# Signal_Multiplexers.net
KiCad netlist of a schematic drawn in Altium Designer
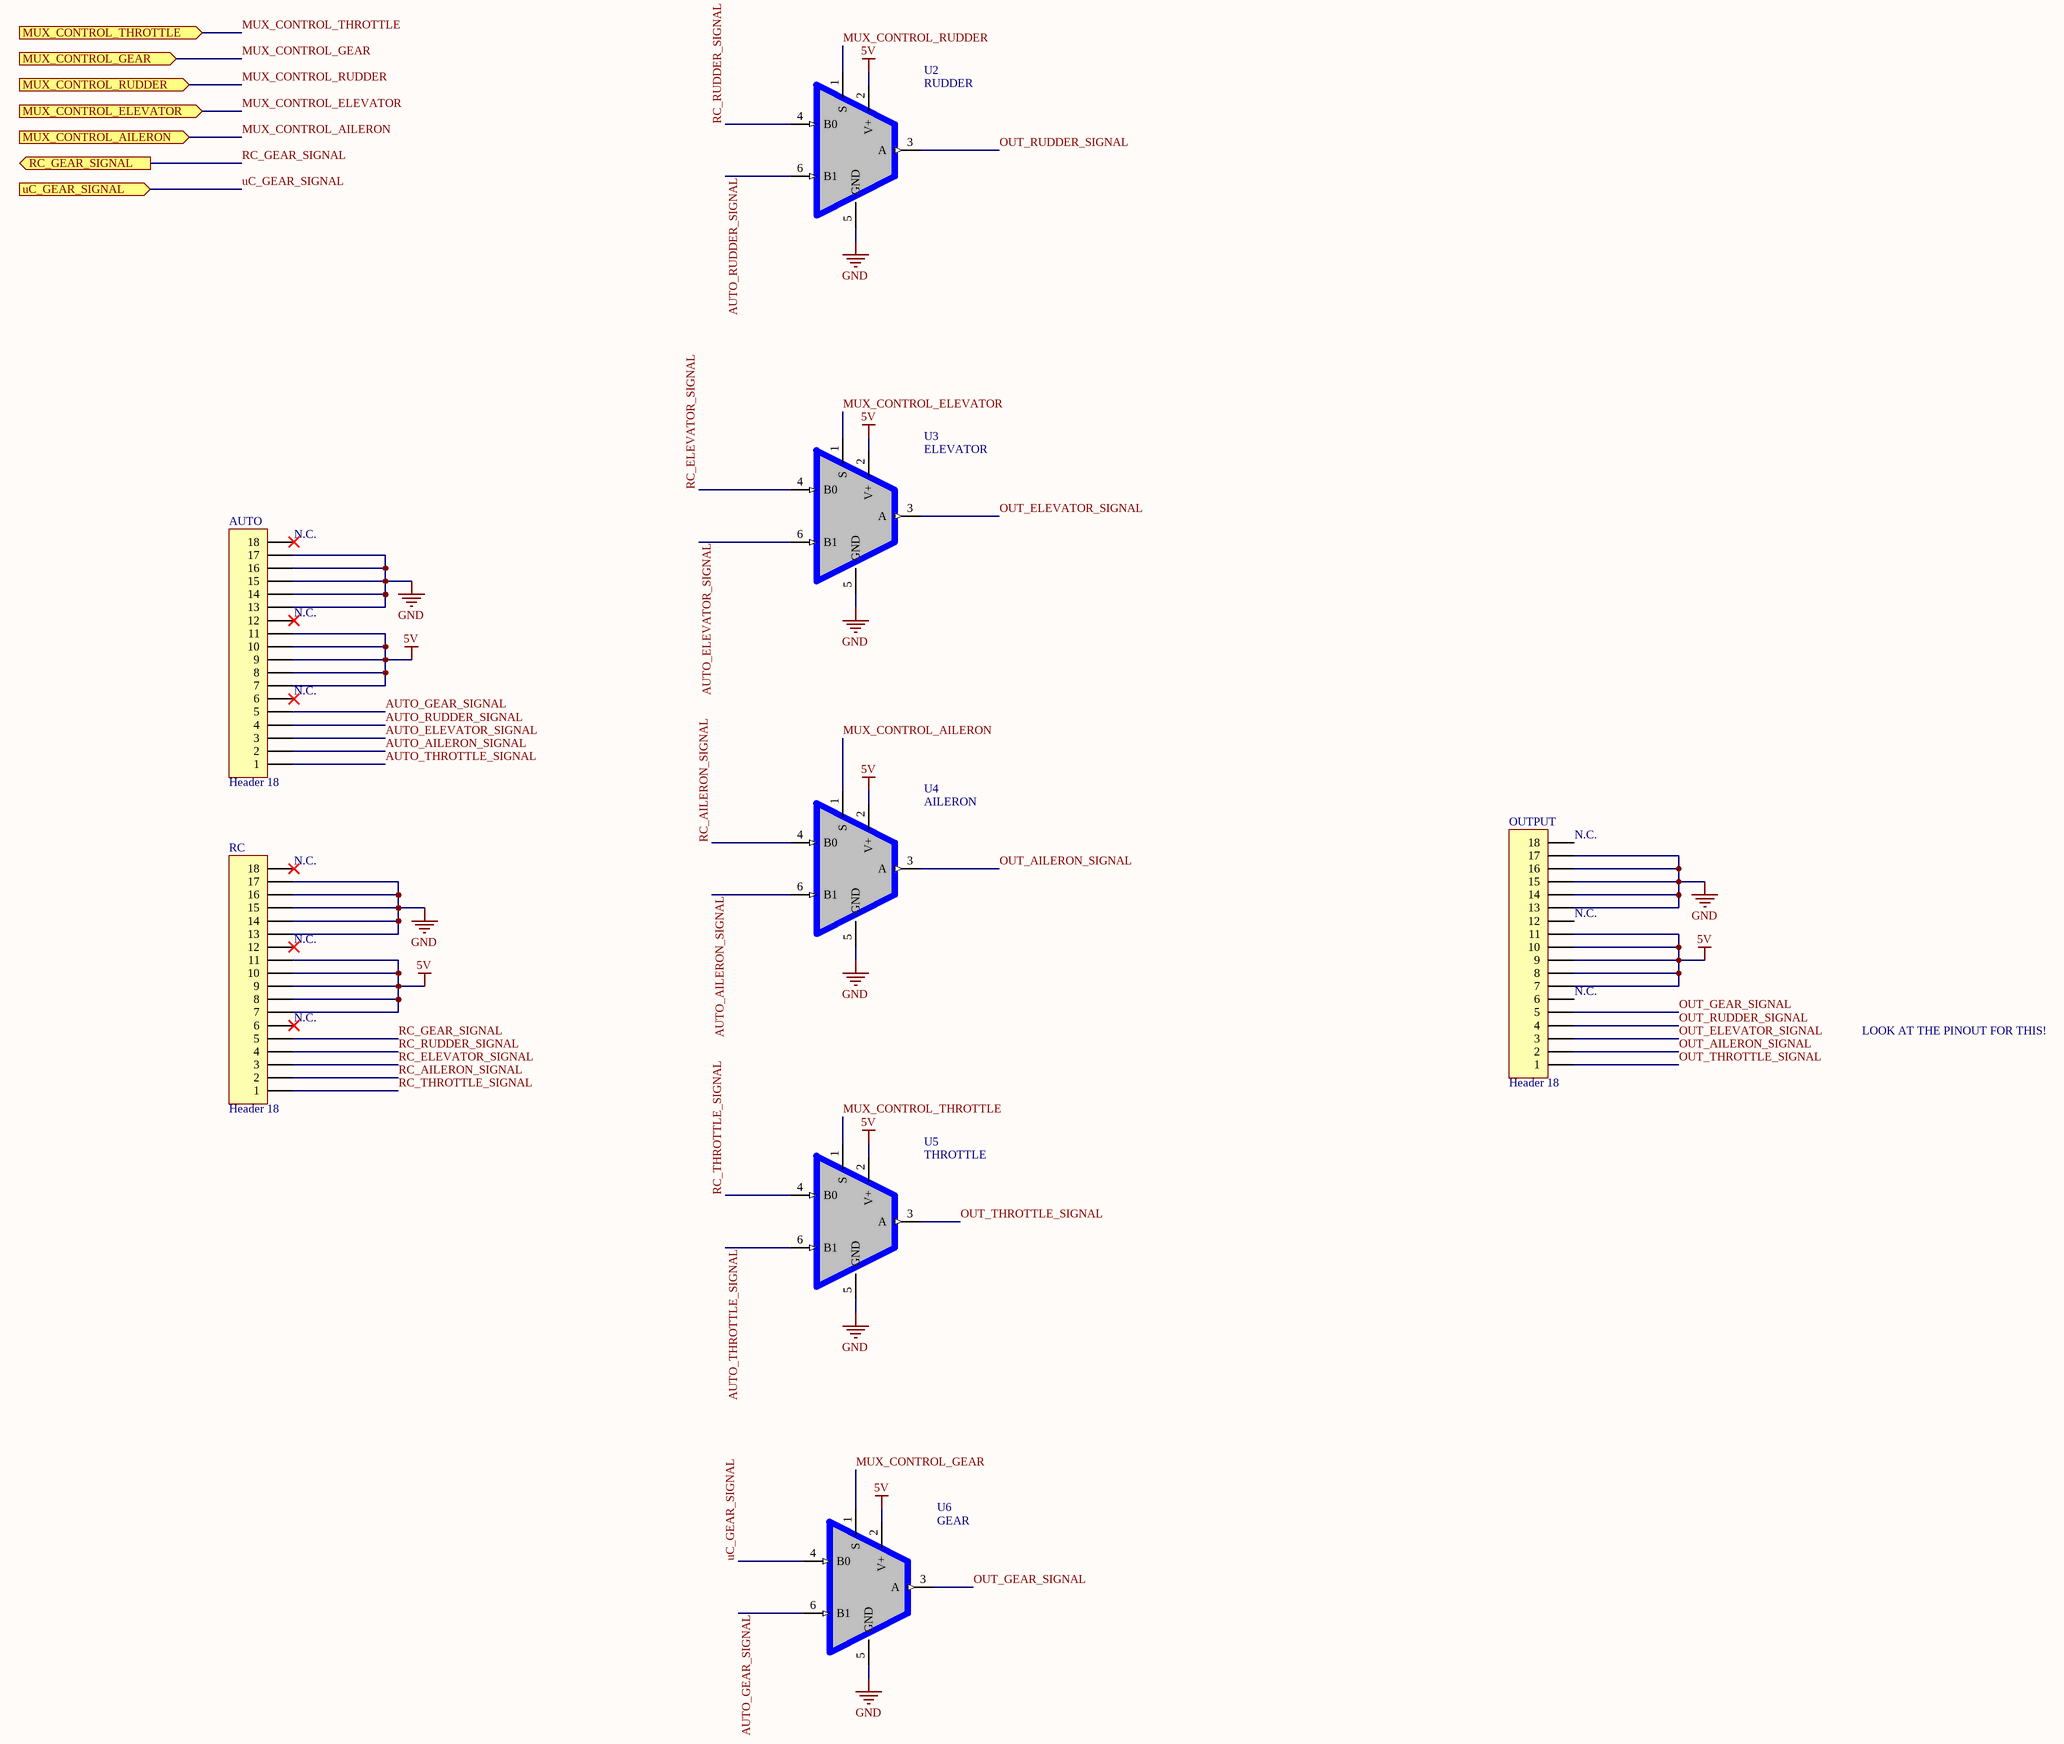
[diagram p0: Signal_Multiplexers.SchDoc]

(export (version "E")
  (design (tool "Eeschema 10.0.6"))
  (components
    (comp (ref "AUTO")
      (value "Header 18")
      (footprint "PCBComponent_1")
      (description "Header, 18-Pin")
      (fields
        (field (name "MANUFACTURER") "Preci-Dip")
        (field (name "MANUFACTURER PART NUMBER") "894-80-030-20-001101")
        (field (name "PUBLISHER") "Altium Limited")
      )
      (libsource (lib "Miscellaneous Connectors") (part "Header 18"))
    )
    (comp (ref "OUTPUT")
      (value "Header 18")
      (footprint "PCBComponent_1")
      (description "Header, 18-Pin")
      (fields
        (field (name "MANUFACTURER") "Preci-Dip")
        (field (name "MANUFACTURER PART NUMBER") "894-80-030-20-001101")
        (field (name "PUBLISHER") "Altium Limited")
      )
      (libsource (lib "Miscellaneous Connectors") (part "Header 18"))
    )
    (comp (ref "RC")
      (value "Header 18")
      (footprint "PCBComponent_1")
      (description "Header, 18-Pin")
      (fields
        (field (name "MANUFACTURER") "Preci-Dip")
        (field (name "MANUFACTURER PART NUMBER") "894-80-030-20-001101")
        (field (name "PUBLISHER") "Altium Limited")
      )
      (libsource (lib "Miscellaneous Connectors") (part "Header 18"))
    )
    (comp (ref "U2")
      (value "RUDDER")
      (footprint "uDFN-6L")
      (description "Multiplexer Switch ICs SPDT 2:1 Mutiplxr 1.65-5.5V; 0.7ohm")
      (libsource (lib "Vishay_Digital_Multiplexers") (part "DG4157EDN"))
    )
    (comp (ref "U3")
      (value "ELEVATOR")
      (footprint "uDFN-6L")
      (description "Multiplexer Switch ICs SPDT 2:1 Mutiplxr 1.65-5.5V; 0.7ohm")
      (libsource (lib "Vishay_Digital_Multiplexers") (part "DG4157EDN"))
    )
    (comp (ref "U4")
      (value "AILERON")
      (footprint "uDFN-6L")
      (description "Multiplexer Switch ICs SPDT 2:1 Mutiplxr 1.65-5.5V; 0.7ohm")
      (libsource (lib "Vishay_Digital_Multiplexers") (part "DG4157EDN"))
    )
    (comp (ref "U5")
      (value "THROTTLE")
      (footprint "uDFN-6L")
      (description "Multiplexer Switch ICs SPDT 2:1 Mutiplxr 1.65-5.5V; 0.7ohm")
      (libsource (lib "Vishay_Digital_Multiplexers") (part "DG4157EDN"))
    )
    (comp (ref "U6")
      (value "GEAR")
      (footprint "uDFN-6L")
      (description "Multiplexer Switch ICs SPDT 2:1 Mutiplxr 1.65-5.5V; 0.7ohm")
      (libsource (lib "Vishay_Digital_Multiplexers") (part "DG4157EDN"))
    )
  )
  (nets
    (net (code "1") (name "/AUTO_AILERON_SIGNAL") (class "Default")
      (node (ref "AUTO") (pin "2") (pinfunction "2_2") (pintype "passive"))
      (node (ref "U4") (pin "6") (pinfunction "B1_6") (pintype "input"))
    )
    (net (code "2") (name "/AUTO_ELEVATOR_SIGNAL") (class "Default")
      (node (ref "AUTO") (pin "3") (pinfunction "3_3") (pintype "passive"))
      (node (ref "U3") (pin "6") (pinfunction "B1_6") (pintype "input"))
    )
    (net (code "3") (name "/AUTO_GEAR_SIGNAL") (class "Default")
      (node (ref "AUTO") (pin "5") (pinfunction "5_5") (pintype "passive"))
      (node (ref "U6") (pin "6") (pinfunction "B1_6") (pintype "input"))
    )
    (net (code "4") (name "/AUTO_RUDDER_SIGNAL") (class "Default")
      (node (ref "AUTO") (pin "4") (pinfunction "4_4") (pintype "passive"))
      (node (ref "U2") (pin "6") (pinfunction "B1_6") (pintype "input"))
    )
    (net (code "5") (name "/AUTO_THROTTLE_SIGNAL") (class "Default")
      (node (ref "AUTO") (pin "1") (pinfunction "1_1") (pintype "passive"))
      (node (ref "U5") (pin "6") (pinfunction "B1_6") (pintype "input"))
    )
    (net (code "6") (name "/MUX_CONTROL_AILERON") (class "Default")
      (node (ref "U4") (pin "1") (pinfunction "S_1") (pintype "passive"))
    )
    (net (code "7") (name "/MUX_CONTROL_ELEVATOR") (class "Default")
      (node (ref "U3") (pin "1") (pinfunction "S_1") (pintype "passive"))
    )
    (net (code "8") (name "/MUX_CONTROL_GEAR") (class "Default")
      (node (ref "U6") (pin "1") (pinfunction "S_1") (pintype "passive"))
    )
    (net (code "9") (name "/MUX_CONTROL_RUDDER") (class "Default")
      (node (ref "U2") (pin "1") (pinfunction "S_1") (pintype "passive"))
    )
    (net (code "10") (name "/MUX_CONTROL_THROTTLE") (class "Default")
      (node (ref "U5") (pin "1") (pinfunction "S_1") (pintype "passive"))
    )
    (net (code "11") (name "/OUT_AILERON_SIGNAL") (class "Default")
      (node (ref "OUTPUT") (pin "2") (pinfunction "2_2") (pintype "passive"))
      (node (ref "U4") (pin "3") (pinfunction "A_3") (pintype "output"))
    )
    (net (code "12") (name "/OUT_ELEVATOR_SIGNAL") (class "Default")
      (node (ref "OUTPUT") (pin "3") (pinfunction "3_3") (pintype "passive"))
      (node (ref "U3") (pin "3") (pinfunction "A_3") (pintype "output"))
    )
    (net (code "13") (name "/OUT_GEAR_SIGNAL") (class "Default")
      (node (ref "OUTPUT") (pin "5") (pinfunction "5_5") (pintype "passive"))
      (node (ref "U6") (pin "3") (pinfunction "A_3") (pintype "output"))
    )
    (net (code "14") (name "/OUT_RUDDER_SIGNAL") (class "Default")
      (node (ref "OUTPUT") (pin "4") (pinfunction "4_4") (pintype "passive"))
      (node (ref "U2") (pin "3") (pinfunction "A_3") (pintype "output"))
    )
    (net (code "15") (name "/OUT_THROTTLE_SIGNAL") (class "Default")
      (node (ref "OUTPUT") (pin "1") (pinfunction "1_1") (pintype "passive"))
      (node (ref "U5") (pin "3") (pinfunction "A_3") (pintype "output"))
    )
    (net (code "16") (name "/RC_AILERON_SIGNAL") (class "Default")
      (node (ref "RC") (pin "2") (pinfunction "2_2") (pintype "passive"))
      (node (ref "U4") (pin "4") (pinfunction "B0_4") (pintype "input"))
    )
    (net (code "17") (name "/RC_ELEVATOR_SIGNAL") (class "Default")
      (node (ref "RC") (pin "3") (pinfunction "3_3") (pintype "passive"))
      (node (ref "U3") (pin "4") (pinfunction "B0_4") (pintype "input"))
    )
    (net (code "18") (name "/RC_GEAR_SIGNAL") (class "Default")
      (node (ref "RC") (pin "5") (pinfunction "5_5") (pintype "passive"))
    )
    (net (code "19") (name "/RC_RUDDER_SIGNAL") (class "Default")
      (node (ref "RC") (pin "4") (pinfunction "4_4") (pintype "passive"))
      (node (ref "U2") (pin "4") (pinfunction "B0_4") (pintype "input"))
    )
    (net (code "20") (name "/RC_THROTTLE_SIGNAL") (class "Default")
      (node (ref "RC") (pin "1") (pinfunction "1_1") (pintype "passive"))
      (node (ref "U5") (pin "4") (pinfunction "B0_4") (pintype "input"))
    )
    (net (code "21") (name "/uC_GEAR_SIGNAL") (class "Default")
      (node (ref "U6") (pin "4") (pinfunction "B0_4") (pintype "input"))
    )
    (net (code "22") (name "5V") (class "Default")
      (node (ref "AUTO") (pin "10") (pinfunction "10_10") (pintype "passive"))
      (node (ref "AUTO") (pin "11") (pinfunction "11_11") (pintype "passive"))
      (node (ref "AUTO") (pin "7") (pinfunction "7_7") (pintype "passive"))
      (node (ref "AUTO") (pin "8") (pinfunction "8_8") (pintype "passive"))
      (node (ref "AUTO") (pin "9") (pinfunction "9_9") (pintype "passive"))
      (node (ref "OUTPUT") (pin "10") (pinfunction "10_10") (pintype "passive"))
      (node (ref "OUTPUT") (pin "11") (pinfunction "11_11") (pintype "passive"))
      (node (ref "OUTPUT") (pin "7") (pinfunction "7_7") (pintype "passive"))
      (node (ref "OUTPUT") (pin "8") (pinfunction "8_8") (pintype "passive"))
      (node (ref "OUTPUT") (pin "9") (pinfunction "9_9") (pintype "passive"))
      (node (ref "RC") (pin "10") (pinfunction "10_10") (pintype "passive"))
      (node (ref "RC") (pin "11") (pinfunction "11_11") (pintype "passive"))
      (node (ref "RC") (pin "7") (pinfunction "7_7") (pintype "passive"))
      (node (ref "RC") (pin "8") (pinfunction "8_8") (pintype "passive"))
      (node (ref "RC") (pin "9") (pinfunction "9_9") (pintype "passive"))
      (node (ref "U2") (pin "2") (pinfunction "V+_2") (pintype "power_in"))
      (node (ref "U3") (pin "2") (pinfunction "V+_2") (pintype "power_in"))
      (node (ref "U4") (pin "2") (pinfunction "V+_2") (pintype "power_in"))
      (node (ref "U5") (pin "2") (pinfunction "V+_2") (pintype "power_in"))
      (node (ref "U6") (pin "2") (pinfunction "V+_2") (pintype "power_in"))
    )
    (net (code "23") (name "GND") (class "Default")
      (node (ref "AUTO") (pin "13") (pinfunction "13_13") (pintype "passive"))
      (node (ref "AUTO") (pin "14") (pinfunction "14_14") (pintype "passive"))
      (node (ref "AUTO") (pin "15") (pinfunction "15_15") (pintype "passive"))
      (node (ref "AUTO") (pin "16") (pinfunction "16_16") (pintype "passive"))
      (node (ref "AUTO") (pin "17") (pinfunction "17_17") (pintype "passive"))
      (node (ref "OUTPUT") (pin "13") (pinfunction "13_13") (pintype "passive"))
      (node (ref "OUTPUT") (pin "14") (pinfunction "14_14") (pintype "passive"))
      (node (ref "OUTPUT") (pin "15") (pinfunction "15_15") (pintype "passive"))
      (node (ref "OUTPUT") (pin "16") (pinfunction "16_16") (pintype "passive"))
      (node (ref "OUTPUT") (pin "17") (pinfunction "17_17") (pintype "passive"))
      (node (ref "RC") (pin "13") (pinfunction "13_13") (pintype "passive"))
      (node (ref "RC") (pin "14") (pinfunction "14_14") (pintype "passive"))
      (node (ref "RC") (pin "15") (pinfunction "15_15") (pintype "passive"))
      (node (ref "RC") (pin "16") (pinfunction "16_16") (pintype "passive"))
      (node (ref "RC") (pin "17") (pinfunction "17_17") (pintype "passive"))
      (node (ref "U2") (pin "5") (pinfunction "GND_5") (pintype "passive"))
      (node (ref "U3") (pin "5") (pinfunction "GND_5") (pintype "passive"))
      (node (ref "U4") (pin "5") (pinfunction "GND_5") (pintype "passive"))
      (node (ref "U5") (pin "5") (pinfunction "GND_5") (pintype "passive"))
      (node (ref "U6") (pin "5") (pinfunction "GND_5") (pintype "passive"))
    )
    (net (code "24") (name "unconnected-(AUTO-Pad6)") (class "Default")
      (node (ref "AUTO") (pin "6") (pinfunction "6_6") (pintype "passive+no_connect"))
    )
    (net (code "25") (name "unconnected-(AUTO-Pad12)") (class "Default")
      (node (ref "AUTO") (pin "12") (pinfunction "12_12") (pintype "passive+no_connect"))
    )
    (net (code "26") (name "unconnected-(AUTO-Pad18)") (class "Default")
      (node (ref "AUTO") (pin "18") (pinfunction "18_18") (pintype "passive+no_connect"))
    )
    (net (code "27") (name "unconnected-(OUTPUT-Pad6)") (class "Default")
      (node (ref "OUTPUT") (pin "6") (pinfunction "6_6") (pintype "passive"))
    )
    (net (code "28") (name "unconnected-(OUTPUT-Pad12)") (class "Default")
      (node (ref "OUTPUT") (pin "12") (pinfunction "12_12") (pintype "passive"))
    )
    (net (code "29") (name "unconnected-(OUTPUT-Pad18)") (class "Default")
      (node (ref "OUTPUT") (pin "18") (pinfunction "18_18") (pintype "passive"))
    )
    (net (code "30") (name "unconnected-(RC-Pad6)") (class "Default")
      (node (ref "RC") (pin "6") (pinfunction "6_6") (pintype "passive+no_connect"))
    )
    (net (code "31") (name "unconnected-(RC-Pad12)") (class "Default")
      (node (ref "RC") (pin "12") (pinfunction "12_12") (pintype "passive+no_connect"))
    )
    (net (code "32") (name "unconnected-(RC-Pad18)") (class "Default")
      (node (ref "RC") (pin "18") (pinfunction "18_18") (pintype "passive+no_connect"))
    )
  )
)
